# ESC_altimeter_v01.net
KiCad netlist of a schematic drawn in Altium Designer
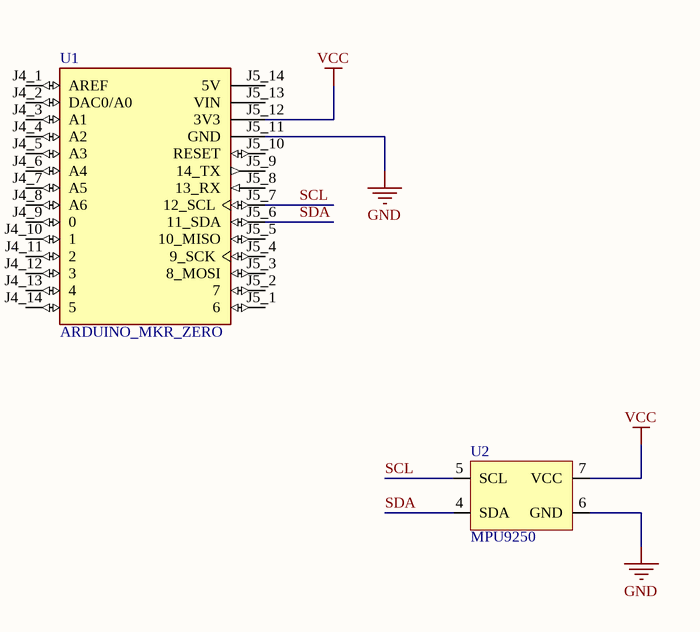
[diagram p0: ESC_altimeter_v01.SchDoc]

(export (version "E")
  (design (tool "Eeschema 10.0.6"))
  (components
    (comp (ref "U1")
      (value "ARDUINO_MKR_ZERO")
      (footprint "MODULE_ARDUINO_MKR_ZERO")
      (description "ATSAMD21 Arduino MKR Zero with Headers SAM D ARMÂ® CortexÂ®-M0+ MCU 32-Bit Embedded Evaluation Board")
      (fields (field (name "MF") "Arduino") (field (name "MP") "ARDUINO MKR ZERO"))
      (libsource (lib "ESC_altimeter_v01") (part "ARDUINO_MKR_ZERO"))
    )
    (comp (ref "U2")
      (value "MPU9250")
      (footprint "MPU9250")
      (libsource (lib "ESC_altimeter_v01") (part "MPU9250"))
    )
  )
  (nets
    (net (code "1") (name "/SCL") (class "Default")
      (node (ref "U1") (pin "J5_7") (pinfunction "12_SCL_J5_7") (pintype "bidirectional"))
      (node (ref "U2") (pin "5") (pinfunction "SCL_5") (pintype "passive"))
    )
    (net (code "2") (name "/SDA") (class "Default")
      (node (ref "U1") (pin "J5_6") (pinfunction "11_SDA_J5_6") (pintype "bidirectional"))
      (node (ref "U2") (pin "4") (pinfunction "SDA_4") (pintype "passive"))
    )
    (net (code "3") (name "GND") (class "Default")
      (node (ref "U1") (pin "J5_11") (pinfunction "GND_J5_11") (pintype "power_in"))
      (node (ref "U2") (pin "6") (pinfunction "GND_6") (pintype "passive"))
    )
    (net (code "4") (name "VCC") (class "Default")
      (node (ref "U1") (pin "J5_12") (pinfunction "3V3_J5_12") (pintype "power_in"))
      (node (ref "U2") (pin "7") (pinfunction "VCC_7") (pintype "passive"))
    )
    (net (code "5") (name "unconnected-(U1-0-PadJ4_9)") (class "Default")
      (node (ref "U1") (pin "J4_9") (pinfunction "0_J4_9") (pintype "bidirectional"))
    )
    (net (code "6") (name "unconnected-(U1-1-PadJ4_10)") (class "Default")
      (node (ref "U1") (pin "J4_10") (pinfunction "1_J4_10") (pintype "bidirectional"))
    )
    (net (code "7") (name "unconnected-(U1-2-PadJ4_11)") (class "Default")
      (node (ref "U1") (pin "J4_11") (pinfunction "2_J4_11") (pintype "bidirectional"))
    )
    (net (code "8") (name "unconnected-(U1-3-PadJ4_12)") (class "Default")
      (node (ref "U1") (pin "J4_12") (pinfunction "3_J4_12") (pintype "bidirectional"))
    )
    (net (code "9") (name "unconnected-(U1-4-PadJ4_13)") (class "Default")
      (node (ref "U1") (pin "J4_13") (pinfunction "4_J4_13") (pintype "bidirectional"))
    )
    (net (code "10") (name "unconnected-(U1-5-PadJ4_14)") (class "Default")
      (node (ref "U1") (pin "J4_14") (pinfunction "5_J4_14") (pintype "bidirectional"))
    )
    (net (code "11") (name "unconnected-(U1-5V-PadJ5_14)") (class "Default")
      (node (ref "U1") (pin "J5_14") (pinfunction "5V_J5_14") (pintype "power_in"))
    )
    (net (code "12") (name "unconnected-(U1-6-PadJ5_1)") (class "Default")
      (node (ref "U1") (pin "J5_1") (pinfunction "6_J5_1") (pintype "bidirectional"))
    )
    (net (code "13") (name "unconnected-(U1-7-PadJ5_2)") (class "Default")
      (node (ref "U1") (pin "J5_2") (pinfunction "7_J5_2") (pintype "bidirectional"))
    )
    (net (code "14") (name "unconnected-(U1-8_MOSI-PadJ5_3)") (class "Default")
      (node (ref "U1") (pin "J5_3") (pinfunction "8_MOSI_J5_3") (pintype "bidirectional"))
    )
    (net (code "15") (name "unconnected-(U1-9_SCK-PadJ5_4)") (class "Default")
      (node (ref "U1") (pin "J5_4") (pinfunction "9_SCK_J5_4") (pintype "bidirectional"))
    )
    (net (code "16") (name "unconnected-(U1-10_MISO-PadJ5_5)") (class "Default")
      (node (ref "U1") (pin "J5_5") (pinfunction "10_MISO_J5_5") (pintype "bidirectional"))
    )
    (net (code "17") (name "unconnected-(U1-13_RX-PadJ5_8)") (class "Default")
      (node (ref "U1") (pin "J5_8") (pinfunction "13_RX_J5_8") (pintype "input"))
    )
    (net (code "18") (name "unconnected-(U1-14_TX-PadJ5_9)") (class "Default")
      (node (ref "U1") (pin "J5_9") (pinfunction "14_TX_J5_9") (pintype "output"))
    )
    (net (code "19") (name "unconnected-(U1-A1-PadJ4_3)") (class "Default")
      (node (ref "U1") (pin "J4_3") (pinfunction "A1_J4_3") (pintype "bidirectional"))
    )
    (net (code "20") (name "unconnected-(U1-A2-PadJ4_4)") (class "Default")
      (node (ref "U1") (pin "J4_4") (pinfunction "A2_J4_4") (pintype "bidirectional"))
    )
    (net (code "21") (name "unconnected-(U1-A3-PadJ4_5)") (class "Default")
      (node (ref "U1") (pin "J4_5") (pinfunction "A3_J4_5") (pintype "bidirectional"))
    )
    (net (code "22") (name "unconnected-(U1-A4-PadJ4_6)") (class "Default")
      (node (ref "U1") (pin "J4_6") (pinfunction "A4_J4_6") (pintype "bidirectional"))
    )
    (net (code "23") (name "unconnected-(U1-A5-PadJ4_7)") (class "Default")
      (node (ref "U1") (pin "J4_7") (pinfunction "A5_J4_7") (pintype "bidirectional"))
    )
    (net (code "24") (name "unconnected-(U1-A6-PadJ4_8)") (class "Default")
      (node (ref "U1") (pin "J4_8") (pinfunction "A6_J4_8") (pintype "bidirectional"))
    )
    (net (code "25") (name "unconnected-(U1-AREF-PadJ4_1)") (class "Default")
      (node (ref "U1") (pin "J4_1") (pinfunction "AREF_J4_1") (pintype "bidirectional"))
    )
    (net (code "26") (name "unconnected-(U1-DAC0{slash}A0-PadJ4_2)") (class "Default")
      (node (ref "U1") (pin "J4_2") (pinfunction "DAC0/A0_J4_2") (pintype "bidirectional"))
    )
    (net (code "27") (name "unconnected-(U1-RESET-PadJ5_10)") (class "Default")
      (node (ref "U1") (pin "J5_10") (pinfunction "RESET_J5_10") (pintype "bidirectional"))
    )
    (net (code "28") (name "unconnected-(U1-VIN-PadJ5_13)") (class "Default")
      (node (ref "U1") (pin "J5_13") (pinfunction "VIN_J5_13") (pintype "power_in"))
    )
  )
)
